# LP5907MFX-3_3NPB.net
KiCad netlist of a schematic drawn in Altium Designer
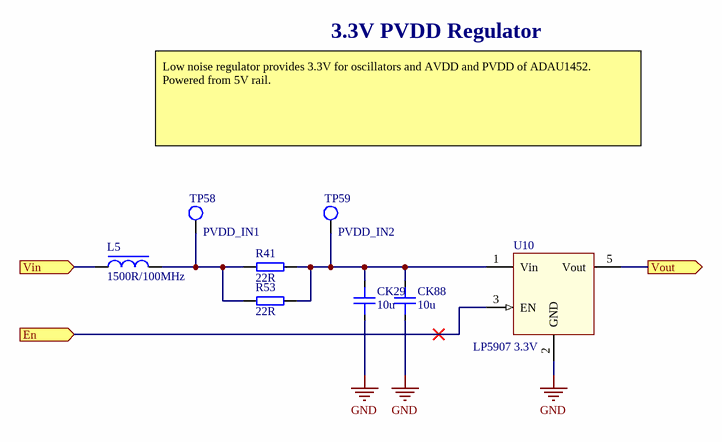
[diagram p0: LP5907MFX-3.3NPB.SchDoc]

(export (version "E")
  (design (tool "Eeschema 10.0.6"))
  (components
    (comp (ref "CK29")
      (value "10u")
      (footprint "CAPC3216X12N(SMC1206)")
      (description "MLCC")
      (fields
        (field (name "TOLERANCE") "10%")
        (field (name "VOLTAGE") "50")
        (field (name "AUTHOR") "JP/10.06.2014")
      )
      (libsource (lib "JP_C") (part "10u-50V-1206-X5R"))
    )
    (comp (ref "CK88")
      (value "10u")
      (footprint "CAPC3216X12N(SMC1206)")
      (description "MLCC")
      (fields
        (field (name "TOLERANCE") "10%")
        (field (name "VOLTAGE") "50")
        (field (name "AUTHOR") "JP/10.06.2014")
      )
      (libsource (lib "JP_C") (part "10u-50V-1206-X5R"))
    )
    (comp (ref "L5")
      (value "1500R/100MHz")
      (footprint "INDC2012X08N(SML0805)")
      (description "Multilayer SMD Ferrite 1500R/100MHz")
      (fields (field (name "AUTHOR") "JP/05.06.2014"))
      (libsource (lib "JP_L") (part "MMZ2012Y152B"))
    )
    (comp (ref "R41")
      (value "22R")
      (footprint "RESC1608X06N(SMR0603)")
      (description "Chip Resistor")
      (fields (field (name "AUTHOR") "JP/10.06.2014"))
      (libsource (lib "JP_R") (part "22R-100mW-0603-ThickFilm"))
    )
    (comp (ref "R53")
      (value "22R")
      (footprint "RESC1608X06N(SMR0603)")
      (description "Chip Resistor")
      (fields (field (name "AUTHOR") "JP/10.06.2014"))
      (libsource (lib "JP_R") (part "22R-100mW-0603-ThickFilm"))
    )
    (comp (ref "TP58")
      (value "PVDD_IN1")
      (footprint "TP_0.8/0.4_ROUND")
      (description "Testpoint - VIA")
      (libsource (lib "JP_CONN") (part "TEST_POINT_VIA"))
    )
    (comp (ref "TP59")
      (value "PVDD_IN2")
      (footprint "TP_0.8/0.4_ROUND")
      (description "Testpoint - VIA")
      (libsource (lib "JP_CONN") (part "TEST_POINT_VIA"))
    )
    (comp (ref "U10")
      (value "LP5907 3.3V")
      (footprint "SOT95P280X90-5N(SOT23-5)")
      (description "Ultra  Low-Noise,  250-mA  Linear  Regulator")
      (libsource (lib "IC") (part "LP5907MFX-3.3NPB"))
    )
  )
  (nets
    (net (code "1") (name "/En") (class "Default")
      (node (ref "U10") (pin "3") (pinfunction "EN_3") (pintype "input"))
    )
    (net (code "2") (name "/Vin") (class "Default") (node (ref "L5") (pin "1") (pintype "passive")))
    (net (code "3") (name "/Vout") (class "Default")
      (node (ref "U10") (pin "5") (pinfunction "Vout_5") (pintype "power_in"))
    )
    (net (code "4") (name "GND") (class "Default")
      (node (ref "CK29") (pin "2") (pinfunction "2_2") (pintype "passive"))
      (node (ref "CK88") (pin "2") (pinfunction "2_2") (pintype "passive"))
      (node (ref "U10") (pin "2") (pinfunction "GND_2") (pintype "power_in"))
    )
    (net (code "5") (name "Net-(L5-Pad2)") (class "Default")
      (node (ref "L5") (pin "2") (pintype "passive"))
      (node (ref "R41") (pin "2") (pinfunction "2_2") (pintype "passive"))
      (node (ref "R53") (pin "2") (pinfunction "2_2") (pintype "passive"))
      (node (ref "TP58") (pin "1") (pintype "passive"))
    )
    (net (code "6") (name "Net-(U10-Vin)") (class "Default")
      (node (ref "CK29") (pin "1") (pinfunction "1_1") (pintype "passive"))
      (node (ref "CK88") (pin "1") (pinfunction "1_1") (pintype "passive"))
      (node (ref "R41") (pin "1") (pinfunction "1_1") (pintype "passive"))
      (node (ref "R53") (pin "1") (pinfunction "1_1") (pintype "passive"))
      (node (ref "TP59") (pin "1") (pintype "passive"))
      (node (ref "U10") (pin "1") (pinfunction "Vin_1") (pintype "power_in"))
    )
  )
)
